# led.net
KiCad netlist of a schematic drawn in EAGLE
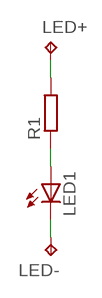
[diagram p0: schematic, sheet 1]

(export (version "E")
  (design (tool "Eeschema 10.0.6"))
  (components
    (comp (ref "LED+")
      (value "TPTP14SQ")
      (footprint "eagle-import:TP14SQ")
      (libsource (lib "eagle-import") (part "TPTP14SQ"))
    )
    (comp (ref "LED-")
      (value "TPTP14SQ")
      (footprint "eagle-import:TP14SQ")
      (libsource (lib "eagle-import") (part "TPTP14SQ"))
    )
    (comp (ref "LED1")
      (value "LEDCHIPLED_0805")
      (footprint "eagle-import:CHIPLED_0805")
      (libsource (lib "eagle-import") (part "LEDCHIPLED_0805"))
    )
    (comp (ref "R1")
      (value "R-EU_M0805")
      (footprint "eagle-import:M0805")
      (libsource (lib "eagle-import") (part "R-EU_M0805"))
    )
  )
  (nets
    (net (code "1") (name "Net-(LED+-PadTP)") (class "Default")
      (node (ref "LED+") (pin "TP") (pinfunction "TP_TP") (pintype "input"))
      (node (ref "R1") (pin "2") (pinfunction "2_2") (pintype "passive"))
    )
    (net (code "2") (name "Net-(LED--PadTP)") (class "Default")
      (node (ref "LED-") (pin "TP") (pinfunction "TP_TP") (pintype "input"))
      (node (ref "LED1") (pin "C") (pinfunction "C_C") (pintype "passive"))
    )
    (net (code "3") (name "Net-(LED1-PadA)") (class "Default")
      (node (ref "LED1") (pin "A") (pinfunction "A_A") (pintype "passive"))
      (node (ref "R1") (pin "1") (pinfunction "1_1") (pintype "passive"))
    )
  )
)
